# qfn-10-socket-pcb-mk-2_0_0-eagle-7_x.net
KiCad netlist of a schematic drawn in EAGLE
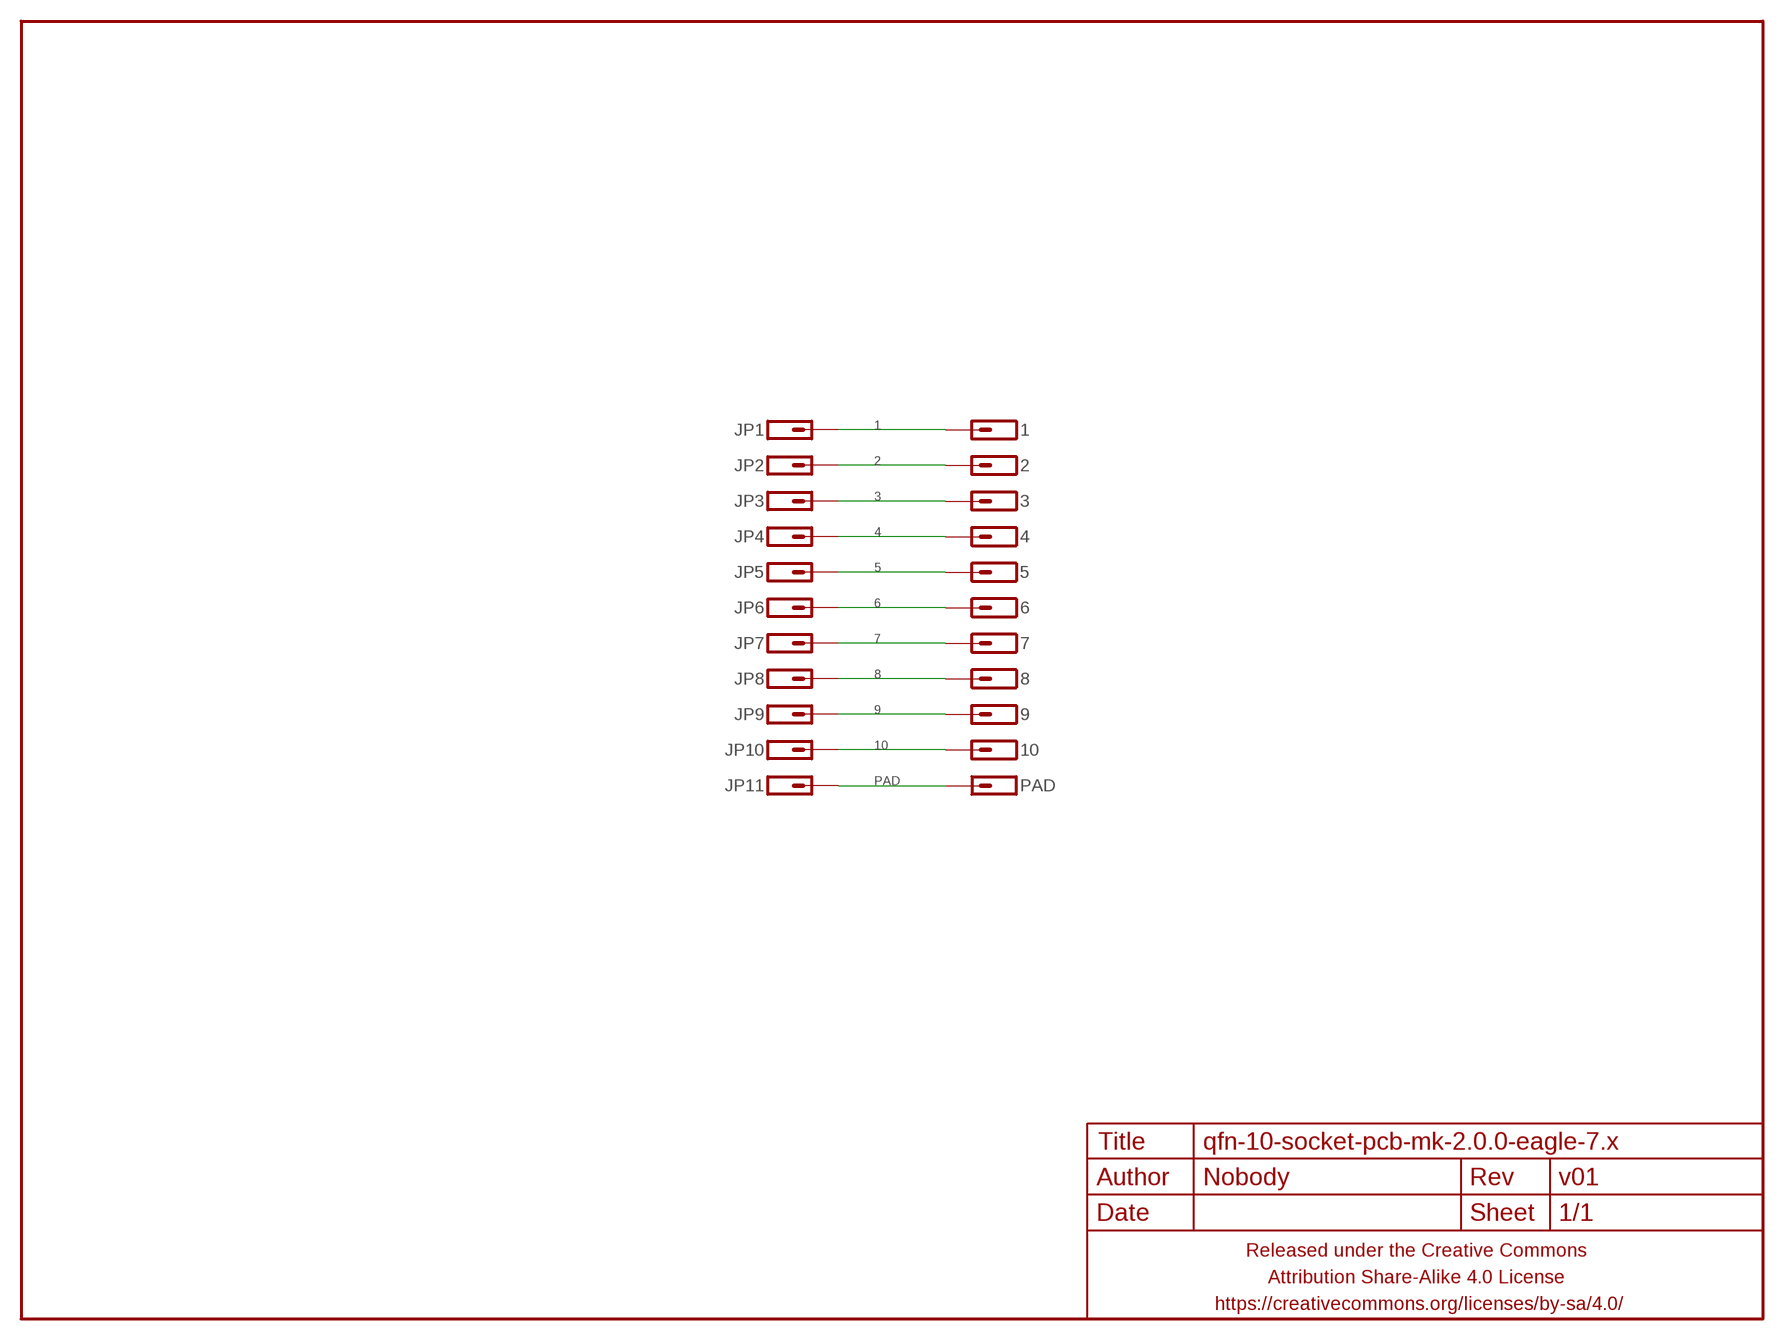
[diagram p0: schematic, sheet 1]

(export (version "E")
  (design (tool "Eeschema 10.0.6"))
  (components
    (comp (ref "1")
      (value "M01PTH")
      (footprint "eagle-import:1X01")
      (libsource (lib "eagle-import") (part "M01PTH"))
    )
    (comp (ref "2")
      (value "M01PTH")
      (footprint "eagle-import:1X01")
      (libsource (lib "eagle-import") (part "M01PTH"))
    )
    (comp (ref "3")
      (value "M01PTH")
      (footprint "eagle-import:1X01")
      (libsource (lib "eagle-import") (part "M01PTH"))
    )
    (comp (ref "4")
      (value "M01PTH")
      (footprint "eagle-import:1X01")
      (libsource (lib "eagle-import") (part "M01PTH"))
    )
    (comp (ref "5")
      (value "M01PTH")
      (footprint "eagle-import:1X01")
      (libsource (lib "eagle-import") (part "M01PTH"))
    )
    (comp (ref "6")
      (value "M01PTH")
      (footprint "eagle-import:1X01")
      (libsource (lib "eagle-import") (part "M01PTH"))
    )
    (comp (ref "7")
      (value "M01PTH")
      (footprint "eagle-import:1X01")
      (libsource (lib "eagle-import") (part "M01PTH"))
    )
    (comp (ref "8")
      (value "M01PTH")
      (footprint "eagle-import:1X01")
      (libsource (lib "eagle-import") (part "M01PTH"))
    )
    (comp (ref "9")
      (value "M01PTH")
      (footprint "eagle-import:1X01")
      (libsource (lib "eagle-import") (part "M01PTH"))
    )
    (comp (ref "10")
      (value "M01PTH")
      (footprint "eagle-import:1X01")
      (libsource (lib "eagle-import") (part "M01PTH"))
    )
    (comp (ref "FRAME1")
      (value "FRAME-LETTERNO_PACKAGE")
      (footprint "eagle-import:DUMMY")
      (fields (field (name "DESIGNER") "Nobody") (field (name "VERSION") "v01"))
      (libsource (lib "eagle-import") (part "FRAME-LETTERNO_PACKAGE"))
    )
    (comp (ref "JP1")
      (value "M01PTH-0.4MM")
      (footprint "eagle-import:1X01-0.4MM")
      (libsource (lib "eagle-import") (part "M01PTH-0.4MM"))
    )
    (comp (ref "JP2")
      (value "M01PTH-0.4MM")
      (footprint "eagle-import:1X01-0.4MM")
      (libsource (lib "eagle-import") (part "M01PTH-0.4MM"))
    )
    (comp (ref "JP3")
      (value "M01PTH-0.4MM")
      (footprint "eagle-import:1X01-0.4MM")
      (libsource (lib "eagle-import") (part "M01PTH-0.4MM"))
    )
    (comp (ref "JP4")
      (value "M01PTH-0.4MM")
      (footprint "eagle-import:1X01-0.4MM")
      (libsource (lib "eagle-import") (part "M01PTH-0.4MM"))
    )
    (comp (ref "JP5")
      (value "M01PTH-0.4MM")
      (footprint "eagle-import:1X01-0.4MM")
      (libsource (lib "eagle-import") (part "M01PTH-0.4MM"))
    )
    (comp (ref "JP6")
      (value "M01PTH-0.4MM")
      (footprint "eagle-import:1X01-0.4MM")
      (libsource (lib "eagle-import") (part "M01PTH-0.4MM"))
    )
    (comp (ref "JP7")
      (value "M01PTH-0.4MM")
      (footprint "eagle-import:1X01-0.4MM")
      (libsource (lib "eagle-import") (part "M01PTH-0.4MM"))
    )
    (comp (ref "JP8")
      (value "M01PTH-0.4MM")
      (footprint "eagle-import:1X01-0.4MM")
      (libsource (lib "eagle-import") (part "M01PTH-0.4MM"))
    )
    (comp (ref "JP9")
      (value "M01PTH-0.4MM")
      (footprint "eagle-import:1X01-0.4MM")
      (libsource (lib "eagle-import") (part "M01PTH-0.4MM"))
    )
    (comp (ref "JP10")
      (value "M01PTH-0.4MM")
      (footprint "eagle-import:1X01-0.4MM")
      (libsource (lib "eagle-import") (part "M01PTH-0.4MM"))
    )
    (comp (ref "JP11")
      (value "M01PTH")
      (footprint "eagle-import:1X01")
      (libsource (lib "eagle-import") (part "M01PTH"))
    )
    (comp (ref "PAD")
      (value "M01PTH-1MM-CIR-NS")
      (footprint "eagle-import:1X01-1MM-CIR-NS")
      (libsource (lib "eagle-import") (part "M01PTH-1MM-CIR-NS"))
    )
  )
  (nets
    (net (code "1") (name "/1") (class "Default")
      (node (ref "1") (pin "1") (pinfunction "1_1") (pintype "passive"))
      (node (ref "JP1") (pin "P$1") (pinfunction "1_P$1") (pintype "passive"))
    )
    (net (code "2") (name "/2") (class "Default")
      (node (ref "2") (pin "1") (pinfunction "1_1") (pintype "passive"))
      (node (ref "JP2") (pin "P$1") (pinfunction "1_P$1") (pintype "passive"))
    )
    (net (code "3") (name "/3") (class "Default")
      (node (ref "3") (pin "1") (pinfunction "1_1") (pintype "passive"))
      (node (ref "JP3") (pin "P$1") (pinfunction "1_P$1") (pintype "passive"))
    )
    (net (code "4") (name "/4") (class "Default")
      (node (ref "4") (pin "1") (pinfunction "1_1") (pintype "passive"))
      (node (ref "JP4") (pin "P$1") (pinfunction "1_P$1") (pintype "passive"))
    )
    (net (code "5") (name "/5") (class "Default")
      (node (ref "5") (pin "1") (pinfunction "1_1") (pintype "passive"))
      (node (ref "JP5") (pin "P$1") (pinfunction "1_P$1") (pintype "passive"))
    )
    (net (code "6") (name "/6") (class "Default")
      (node (ref "6") (pin "1") (pinfunction "1_1") (pintype "passive"))
      (node (ref "JP6") (pin "P$1") (pinfunction "1_P$1") (pintype "passive"))
    )
    (net (code "7") (name "/7") (class "Default")
      (node (ref "7") (pin "1") (pinfunction "1_1") (pintype "passive"))
      (node (ref "JP7") (pin "P$1") (pinfunction "1_P$1") (pintype "passive"))
    )
    (net (code "8") (name "/8") (class "Default")
      (node (ref "8") (pin "1") (pinfunction "1_1") (pintype "passive"))
      (node (ref "JP8") (pin "P$1") (pinfunction "1_P$1") (pintype "passive"))
    )
    (net (code "9") (name "/9") (class "Default")
      (node (ref "9") (pin "1") (pinfunction "1_1") (pintype "passive"))
      (node (ref "JP9") (pin "P$1") (pinfunction "1_P$1") (pintype "passive"))
    )
    (net (code "10") (name "/10") (class "Default")
      (node (ref "10") (pin "1") (pinfunction "1_1") (pintype "passive"))
      (node (ref "JP10") (pin "P$1") (pinfunction "1_P$1") (pintype "passive"))
    )
    (net (code "11") (name "/PAD") (class "Default")
      (node (ref "JP11") (pin "1") (pinfunction "1_1") (pintype "passive"))
      (node (ref "PAD") (pin "1") (pinfunction "1_1") (pintype "passive"))
    )
  )
)
